# power_proto_routed.net
KiCad netlist of a schematic drawn in EAGLE
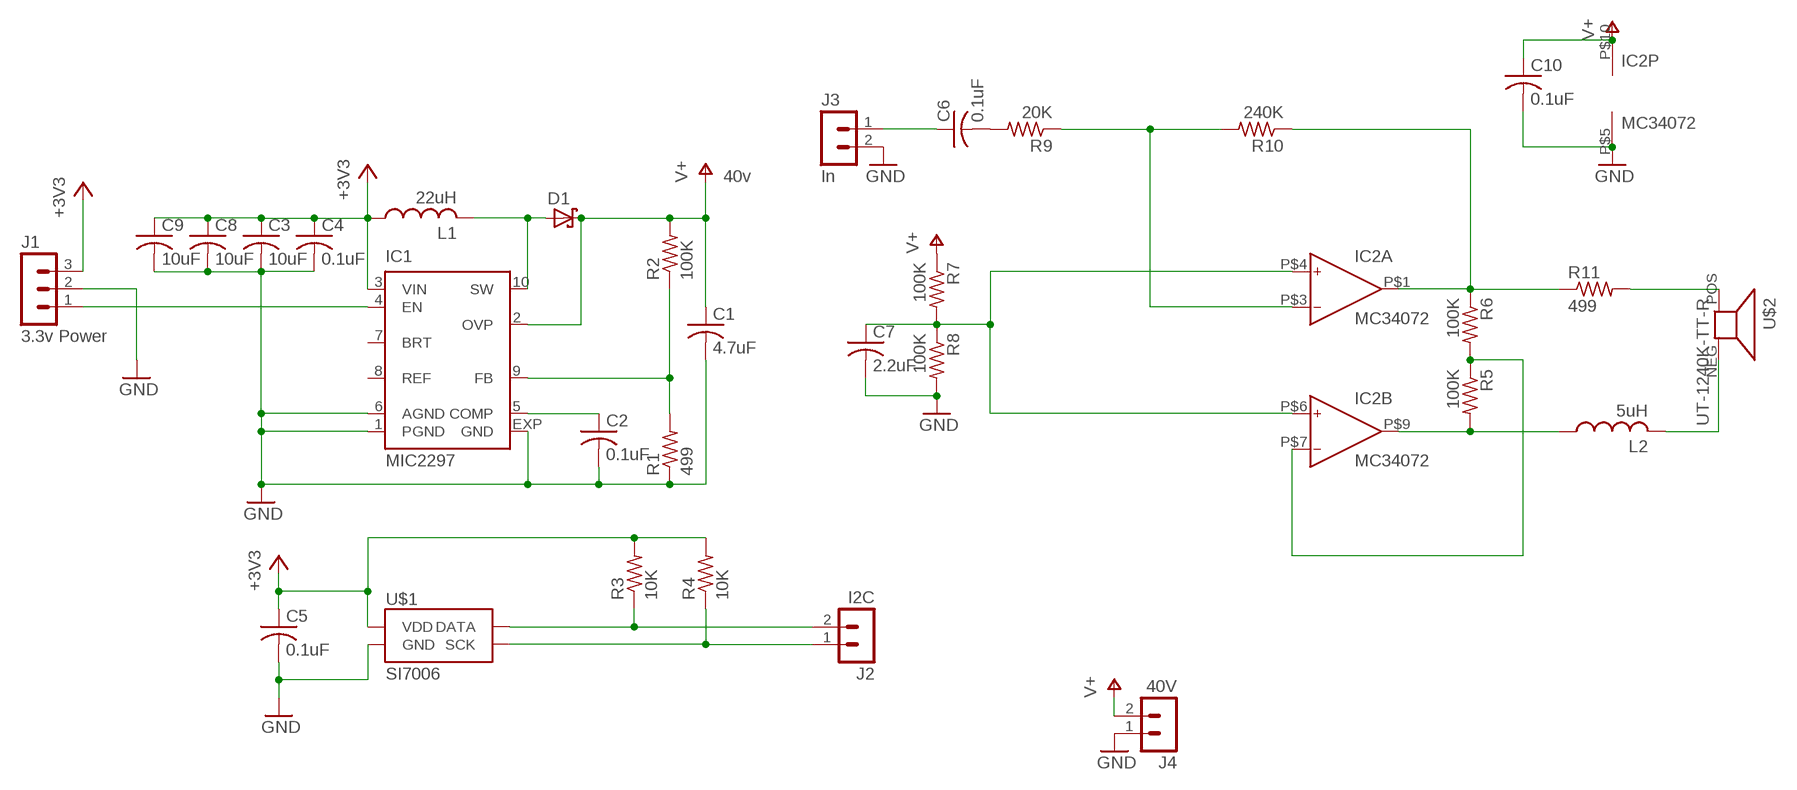
[diagram p0: schematic, sheet 1]

(export (version "E")
  (design (tool "Eeschema 10.0.6"))
  (components
    (comp (ref "C1")
      (value "4.7uF")
      (footprint "eagle-import:C0805")
      (libsource (lib "eagle-import") (part "C-USC0805"))
    )
    (comp (ref "C2")
      (value "0.1uF")
      (footprint "eagle-import:C0805")
      (libsource (lib "eagle-import") (part "C-USC0805"))
    )
    (comp (ref "C3")
      (value "10uF")
      (footprint "eagle-import:C0805")
      (libsource (lib "eagle-import") (part "C-USC0805"))
    )
    (comp (ref "C4")
      (value "0.1uF")
      (footprint "eagle-import:C0805")
      (libsource (lib "eagle-import") (part "C-USC0805"))
    )
    (comp (ref "C5")
      (value "0.1uF")
      (footprint "eagle-import:C0805")
      (libsource (lib "eagle-import") (part "C-USC0805"))
    )
    (comp (ref "C6")
      (value "0.1uF")
      (footprint "eagle-import:C0805")
      (libsource (lib "eagle-import") (part "C-USC0805"))
    )
    (comp (ref "C7")
      (value "2.2uF")
      (footprint "eagle-import:C0805")
      (libsource (lib "eagle-import") (part "C-USC0805"))
    )
    (comp (ref "C8")
      (value "10uF")
      (footprint "eagle-import:C0805")
      (libsource (lib "eagle-import") (part "C-USC0805"))
    )
    (comp (ref "C9")
      (value "10uF")
      (footprint "eagle-import:C0805")
      (libsource (lib "eagle-import") (part "C-USC0805"))
    )
    (comp (ref "C10")
      (value "0.1uF")
      (footprint "eagle-import:C0805")
      (libsource (lib "eagle-import") (part "C-USC0805"))
    )
    (comp (ref "D1")
      (value "DIODE_SCHOTTKYMICROSMP")
      (footprint "eagle-import:DIODE_SCHOTTKY_MICROSMP")
      (libsource (lib "eagle-import") (part "DIODE_SCHOTTKYMICROSMP"))
    )
    (comp (ref "IC1")
      (value "MIC2297")
      (footprint "eagle-import:MLF10")
      (fields (field (name "MPN") "MIC2297-38YML TR"))
      (libsource (lib "eagle-import") (part "MIC2297"))
    )
    (comp (ref "IC2")
      (value "MC34072")
      (footprint "eagle-import:WQFN10")
      (libsource (lib "eagle-import") (part "MC34072"))
    )
    (comp (ref "J1")
      (value "3.3v Power")
      (footprint "eagle-import:MA03-1")
      (libsource (lib "eagle-import") (part "MA03-1"))
    )
    (comp (ref "J2")
      (value "I2C")
      (footprint "eagle-import:MA02-1")
      (libsource (lib "eagle-import") (part "MA02-1"))
    )
    (comp (ref "J3")
      (value "In")
      (footprint "eagle-import:MA02-1")
      (libsource (lib "eagle-import") (part "MA02-1"))
    )
    (comp (ref "J4")
      (value "40V")
      (footprint "eagle-import:MA02-1")
      (libsource (lib "eagle-import") (part "MA02-1"))
    )
    (comp (ref "L1")
      (value "22uH")
      (footprint "eagle-import:INDUCTOR_BOURNS_SRN3012TA")
      (libsource (lib "eagle-import") (part "INDUCTOR7"))
    )
    (comp (ref "L2")
      (value "5uH")
      (footprint "eagle-import:INDUCTOR_BOURNS_SDR0503")
      (libsource (lib "eagle-import") (part "INDUCTOR"))
    )
    (comp (ref "R1")
      (value "499")
      (footprint "eagle-import:R0805")
      (libsource (lib "eagle-import") (part "R-US_R0805"))
    )
    (comp (ref "R2")
      (value "100K")
      (footprint "eagle-import:R0805")
      (libsource (lib "eagle-import") (part "R-US_R0805"))
    )
    (comp (ref "R3")
      (value "10K")
      (footprint "eagle-import:R0805")
      (libsource (lib "eagle-import") (part "R-US_R0805"))
    )
    (comp (ref "R4")
      (value "10K")
      (footprint "eagle-import:R0805")
      (libsource (lib "eagle-import") (part "R-US_R0805"))
    )
    (comp (ref "R5")
      (value "100K")
      (footprint "eagle-import:R0805")
      (libsource (lib "eagle-import") (part "R-US_R0805"))
    )
    (comp (ref "R6")
      (value "100K")
      (footprint "eagle-import:R0805")
      (libsource (lib "eagle-import") (part "R-US_R0805"))
    )
    (comp (ref "R7")
      (value "100K")
      (footprint "eagle-import:R0805")
      (libsource (lib "eagle-import") (part "R-US_R0805"))
    )
    (comp (ref "R8")
      (value "100K")
      (footprint "eagle-import:R0805")
      (libsource (lib "eagle-import") (part "R-US_R0805"))
    )
    (comp (ref "R9")
      (value "20K")
      (footprint "eagle-import:R0805")
      (libsource (lib "eagle-import") (part "R-US_R0805"))
    )
    (comp (ref "R10")
      (value "240K")
      (footprint "eagle-import:R0805")
      (libsource (lib "eagle-import") (part "R-US_R0805"))
    )
    (comp (ref "R11")
      (value "499")
      (footprint "eagle-import:R0805")
      (libsource (lib "eagle-import") (part "R-US_R0805"))
    )
    (comp (ref "U$1")
      (value "SI7006")
      (footprint "eagle-import:SI7006")
      (libsource (lib "eagle-import") (part "SI7006"))
    )
    (comp (ref "U$2")
      (value "UT-1240K-TT-R")
      (footprint "eagle-import:UT-1240K-TT-R")
      (libsource (lib "eagle-import") (part "UT-1240K-TT-R"))
    )
  )
  (nets
    (net (code "1") (name "+3V3") (class "Default")
      (node (ref "C3") (pin "1") (pinfunction "1_1") (pintype "passive"))
      (node (ref "C4") (pin "1") (pinfunction "1_1") (pintype "passive"))
      (node (ref "C5") (pin "1") (pinfunction "1_1") (pintype "passive"))
      (node (ref "C8") (pin "1") (pinfunction "1_1") (pintype "passive"))
      (node (ref "C9") (pin "1") (pinfunction "1_1") (pintype "passive"))
      (node (ref "IC1") (pin "3") (pinfunction "VIN_3") (pintype "input"))
      (node (ref "J1") (pin "3") (pinfunction "3_3") (pintype "passive"))
      (node (ref "L1") (pin "P$1") (pinfunction "1_P$1") (pintype "passive"))
      (node (ref "R3") (pin "2") (pinfunction "2_2") (pintype "passive"))
      (node (ref "R4") (pin "2") (pinfunction "2_2") (pintype "passive"))
      (node (ref "U$1") (pin "VDD") (pinfunction "VDD_VDD") (pintype "power_in"))
    )
    (net (code "2") (name "GND") (class "Default")
      (node (ref "C1") (pin "2") (pinfunction "2_2") (pintype "passive"))
      (node (ref "C10") (pin "2") (pinfunction "2_2") (pintype "passive"))
      (node (ref "C2") (pin "2") (pinfunction "2_2") (pintype "passive"))
      (node (ref "C3") (pin "2") (pinfunction "2_2") (pintype "passive"))
      (node (ref "C4") (pin "2") (pinfunction "2_2") (pintype "passive"))
      (node (ref "C5") (pin "2") (pinfunction "2_2") (pintype "passive"))
      (node (ref "C7") (pin "2") (pinfunction "2_2") (pintype "passive"))
      (node (ref "C8") (pin "2") (pinfunction "2_2") (pintype "passive"))
      (node (ref "C9") (pin "2") (pinfunction "2_2") (pintype "passive"))
      (node (ref "IC1") (pin "1") (pinfunction "PGND_1") (pintype "input"))
      (node (ref "IC1") (pin "6") (pinfunction "AGND_6") (pintype "input"))
      (node (ref "IC1") (pin "EXP") (pinfunction "GND_EXP") (pintype "input"))
      (node (ref "IC2") (pin "P$5") (pinfunction "V-_P$5") (pintype "power_in"))
      (node (ref "J1") (pin "2") (pinfunction "2_2") (pintype "passive"))
      (node (ref "J3") (pin "2") (pinfunction "2_2") (pintype "passive"))
      (node (ref "J4") (pin "1") (pinfunction "1_1") (pintype "passive"))
      (node (ref "R1") (pin "1") (pinfunction "1_1") (pintype "passive"))
      (node (ref "R8") (pin "2") (pinfunction "2_2") (pintype "passive"))
      (node (ref "U$1") (pin "GND") (pinfunction "GND_GND") (pintype "power_in"))
    )
    (net (code "3") (name "Net-(C6-Pad1)") (class "Default")
      (node (ref "C6") (pin "1") (pinfunction "1_1") (pintype "passive"))
      (node (ref "J3") (pin "1") (pinfunction "1_1") (pintype "passive"))
    )
    (net (code "4") (name "Net-(C6-Pad2)") (class "Default")
      (node (ref "C6") (pin "2") (pinfunction "2_2") (pintype "passive"))
      (node (ref "R9") (pin "2") (pinfunction "2_2") (pintype "passive"))
    )
    (net (code "5") (name "Net-(IC1-COMP)") (class "Default")
      (node (ref "C2") (pin "1") (pinfunction "1_1") (pintype "passive"))
      (node (ref "IC1") (pin "5") (pinfunction "COMP_5") (pintype "passive"))
    )
    (net (code "6") (name "Net-(IC1-EN)") (class "Default")
      (node (ref "IC1") (pin "4") (pinfunction "EN_4") (pintype "input"))
      (node (ref "J1") (pin "1") (pinfunction "1_1") (pintype "passive"))
    )
    (net (code "7") (name "Net-(IC1-FB)") (class "Default")
      (node (ref "IC1") (pin "9") (pinfunction "FB_9") (pintype "input"))
      (node (ref "R1") (pin "2") (pinfunction "2_2") (pintype "passive"))
      (node (ref "R2") (pin "1") (pinfunction "1_1") (pintype "passive"))
    )
    (net (code "8") (name "Net-(IC1-SW)") (class "Default")
      (node (ref "D1") (pin "A") (pinfunction "A_A") (pintype "passive"))
      (node (ref "IC1") (pin "10") (pinfunction "SW_10") (pintype "open_collector"))
      (node (ref "L1") (pin "P$2") (pinfunction "2_P$2") (pintype "passive"))
    )
    (net (code "9") (name "Net-(IC2A-IN+)") (class "Default")
      (node (ref "C7") (pin "1") (pinfunction "1_1") (pintype "passive"))
      (node (ref "IC2") (pin "P$4") (pinfunction "IN+_P$4") (pintype "input"))
      (node (ref "IC2") (pin "P$6") (pinfunction "IN+_P$6") (pintype "input"))
      (node (ref "R7") (pin "2") (pinfunction "2_2") (pintype "passive"))
      (node (ref "R8") (pin "1") (pinfunction "1_1") (pintype "passive"))
    )
    (net (code "10") (name "Net-(IC2A-IN-)") (class "Default")
      (node (ref "IC2") (pin "P$3") (pinfunction "IN-_P$3") (pintype "input"))
      (node (ref "R10") (pin "2") (pinfunction "2_2") (pintype "passive"))
      (node (ref "R9") (pin "1") (pinfunction "1_1") (pintype "passive"))
    )
    (net (code "11") (name "Net-(IC2A-OUT)") (class "Default")
      (node (ref "IC2") (pin "P$1") (pinfunction "OUT_P$1") (pintype "output"))
      (node (ref "R10") (pin "1") (pinfunction "1_1") (pintype "passive"))
      (node (ref "R11") (pin "1") (pinfunction "1_1") (pintype "passive"))
      (node (ref "R6") (pin "1") (pinfunction "1_1") (pintype "passive"))
    )
    (net (code "12") (name "Net-(IC2B-IN-)") (class "Default")
      (node (ref "IC2") (pin "P$7") (pinfunction "IN-_P$7") (pintype "input"))
      (node (ref "R5") (pin "1") (pinfunction "1_1") (pintype "passive"))
      (node (ref "R6") (pin "2") (pinfunction "2_2") (pintype "passive"))
    )
    (net (code "13") (name "Net-(IC2B-OUT)") (class "Default")
      (node (ref "IC2") (pin "P$9") (pinfunction "OUT_P$9") (pintype "output"))
      (node (ref "L2") (pin "1") (pinfunction "1_1") (pintype "passive"))
      (node (ref "R5") (pin "2") (pinfunction "2_2") (pintype "passive"))
    )
    (net (code "14") (name "Net-(J2-Pad1)") (class "Default")
      (node (ref "J2") (pin "1") (pinfunction "1_1") (pintype "passive"))
      (node (ref "R4") (pin "1") (pinfunction "1_1") (pintype "passive"))
      (node (ref "U$1") (pin "SCK") (pinfunction "SCK_SCK") (pintype "input"))
    )
    (net (code "15") (name "Net-(J2-Pad2)") (class "Default")
      (node (ref "J2") (pin "2") (pinfunction "2_2") (pintype "passive"))
      (node (ref "R3") (pin "1") (pinfunction "1_1") (pintype "passive"))
      (node (ref "U$1") (pin "DATA") (pinfunction "DATA_DATA") (pintype "bidirectional"))
    )
    (net (code "16") (name "Net-(L2-Pad2)") (class "Default")
      (node (ref "L2") (pin "2") (pinfunction "2_2") (pintype "passive"))
      (node (ref "U$2") (pin "NEG") (pinfunction "NEG_NEG") (pintype "passive"))
    )
    (net (code "17") (name "Net-(R11-Pad2)") (class "Default")
      (node (ref "R11") (pin "2") (pinfunction "2_2") (pintype "passive"))
      (node (ref "U$2") (pin "POS") (pinfunction "POS_POS") (pintype "passive"))
    )
    (net (code "18") (name "V+") (class "Default")
      (node (ref "C1") (pin "1") (pinfunction "1_1") (pintype "passive"))
      (node (ref "C10") (pin "1") (pinfunction "1_1") (pintype "passive"))
      (node (ref "D1") (pin "C") (pinfunction "C_C") (pintype "passive"))
      (node (ref "IC1") (pin "2") (pinfunction "OVP_2") (pintype "input"))
      (node (ref "IC2") (pin "P$10") (pinfunction "V+_P$10") (pintype "power_in"))
      (node (ref "J4") (pin "2") (pinfunction "2_2") (pintype "passive"))
      (node (ref "R2") (pin "2") (pinfunction "2_2") (pintype "passive"))
      (node (ref "R7") (pin "1") (pinfunction "1_1") (pintype "passive"))
    )
    (net (code "19") (name "unconnected-(IC1-BRT-Pad7)") (class "Default")
      (node (ref "IC1") (pin "7") (pinfunction "BRT_7") (pintype "input"))
    )
    (net (code "20") (name "unconnected-(IC1-REF-Pad8)") (class "Default")
      (node (ref "IC1") (pin "8") (pinfunction "REF_8") (pintype "input"))
    )
  )
)
